# StaticPlatformMain_v1.net
KiCad netlist of a schematic drawn in EAGLE
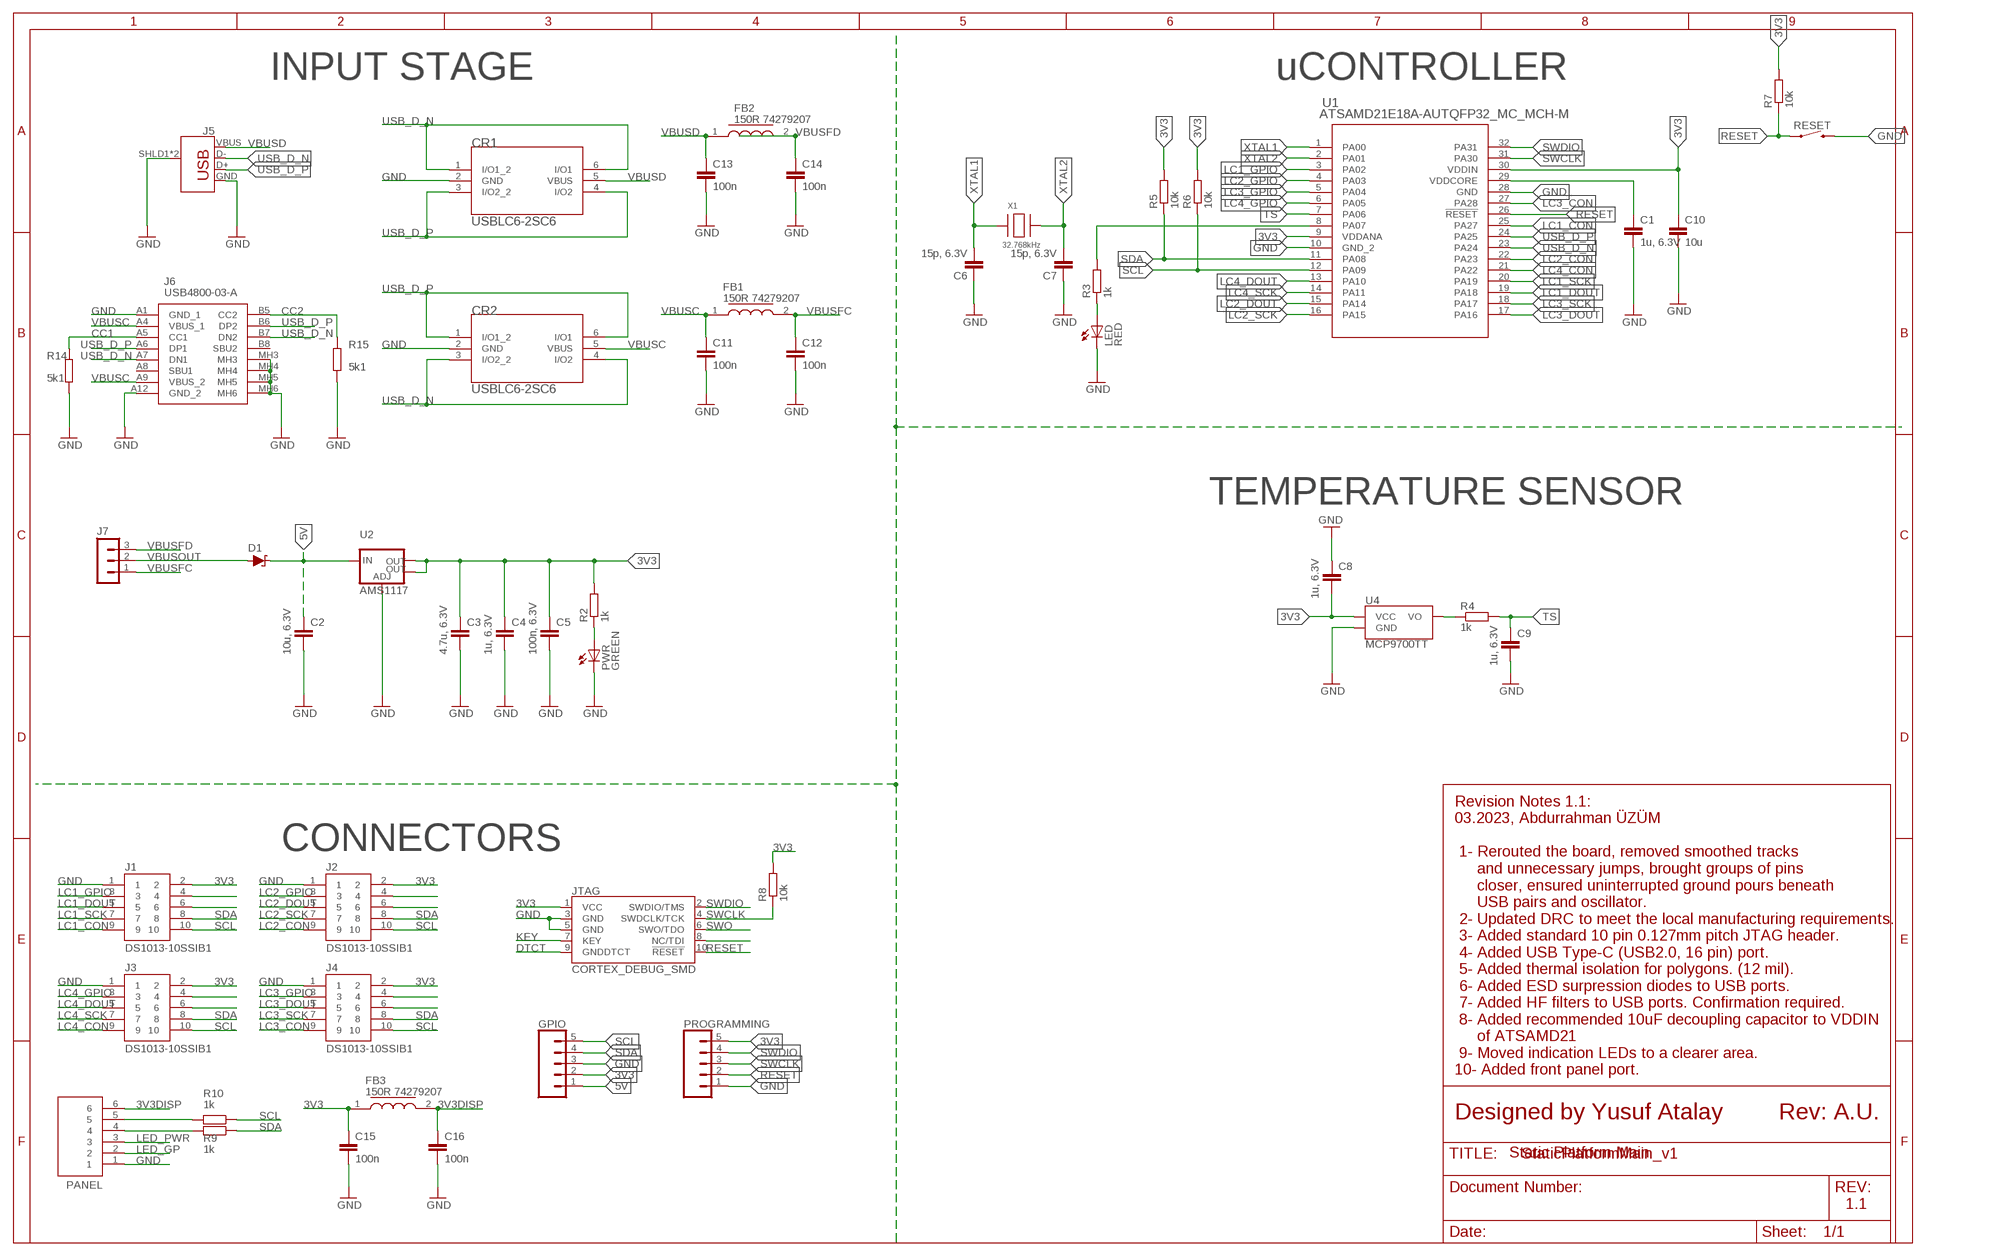
[diagram p0: schematic, sheet 1]

(export (version "E")
  (design (tool "Eeschema 10.0.6"))
  (components
    (comp (ref "C1")
      (value "1u, 6.3V")
      (footprint "eagle-import:C0805")
      (libsource (lib "eagle-import") (part "C-EUC0805"))
    )
    (comp (ref "C2")
      (value "10u, 6.3V")
      (footprint "eagle-import:C0805")
      (libsource (lib "eagle-import") (part "C-EUC0805"))
    )
    (comp (ref "C3")
      (value "4.7u, 6.3V")
      (footprint "eagle-import:C0805")
      (libsource (lib "eagle-import") (part "C-EUC0805"))
    )
    (comp (ref "C4")
      (value "1u, 6.3V")
      (footprint "eagle-import:C0805")
      (libsource (lib "eagle-import") (part "C-EUC0805"))
    )
    (comp (ref "C5")
      (value "100n, 6.3V")
      (footprint "eagle-import:C0805")
      (libsource (lib "eagle-import") (part "C-EUC0805"))
    )
    (comp (ref "C6")
      (value "15p, 6.3V")
      (footprint "eagle-import:C0805")
      (libsource (lib "eagle-import") (part "C-EUC0805"))
    )
    (comp (ref "C7")
      (value "15p, 6.3V")
      (footprint "eagle-import:C0805")
      (libsource (lib "eagle-import") (part "C-EUC0805"))
    )
    (comp (ref "C8")
      (value "1u, 6.3V")
      (footprint "eagle-import:C0805")
      (libsource (lib "eagle-import") (part "C-EUC0805"))
    )
    (comp (ref "C9")
      (value "1u, 6.3V")
      (footprint "eagle-import:C0805")
      (libsource (lib "eagle-import") (part "C-EUC0805"))
    )
    (comp (ref "C10")
      (value "10u")
      (footprint "eagle-import:C0805")
      (libsource (lib "eagle-import") (part "C-EUC0805"))
    )
    (comp (ref "C11")
      (value "100n")
      (footprint "eagle-import:C0805")
      (libsource (lib "eagle-import") (part "C-EUC0805"))
    )
    (comp (ref "C12")
      (value "100n")
      (footprint "eagle-import:C0805")
      (libsource (lib "eagle-import") (part "C-EUC0805"))
    )
    (comp (ref "C13")
      (value "100n")
      (footprint "eagle-import:C0805")
      (libsource (lib "eagle-import") (part "C-EUC0805"))
    )
    (comp (ref "C14")
      (value "100n")
      (footprint "eagle-import:C0805")
      (libsource (lib "eagle-import") (part "C-EUC0805"))
    )
    (comp (ref "C15")
      (value "100n")
      (footprint "eagle-import:C0805")
      (libsource (lib "eagle-import") (part "C-EUC0805"))
    )
    (comp (ref "C16")
      (value "100n")
      (footprint "eagle-import:C0805")
      (libsource (lib "eagle-import") (part "C-EUC0805"))
    )
    (comp (ref "CR1")
      (value "USBLC6-2SC6")
      (footprint "eagle-import:SOT23-6L_STM")
      (fields (field (name "COPYRIGHT") "Copyright (C) 2023 Ultra Librarian. All rights reserved."))
      (libsource (lib "eagle-import") (part "USBLC6-2SC6"))
    )
    (comp (ref "CR2")
      (value "USBLC6-2SC6")
      (footprint "eagle-import:SOT23-6L_STM")
      (fields (field (name "COPYRIGHT") "Copyright (C) 2023 Ultra Librarian. All rights reserved."))
      (libsource (lib "eagle-import") (part "USBLC6-2SC6"))
    )
    (comp (ref "D1")
      (value "3A/10V/280mV")
      (footprint "eagle-import:SOD-323")
      (libsource (lib "eagle-import") (part "DIODE-SCHOTTKY-BAT60A"))
    )
    (comp (ref "FB1")
      (value "150R 74279207")
      (footprint "eagle-import:CAPC2012X90N")
      (fields
        (field (name "MANUFACTURER_PART_NUMBER") "74279207")
        (field (name "MOUSER_PART_NUMBER") "710-74279207")
      )
      (libsource (lib "eagle-import") (part "74279207"))
    )
    (comp (ref "FB2")
      (value "150R 74279207")
      (footprint "eagle-import:CAPC2012X90N")
      (fields
        (field (name "MANUFACTURER_PART_NUMBER") "74279207")
        (field (name "MOUSER_PART_NUMBER") "710-74279207")
      )
      (libsource (lib "eagle-import") (part "74279207"))
    )
    (comp (ref "FB3")
      (value "150R 74279207")
      (footprint "eagle-import:CAPC2012X90N")
      (fields
        (field (name "MANUFACTURER_PART_NUMBER") "74279207")
        (field (name "MOUSER_PART_NUMBER") "710-74279207")
      )
      (libsource (lib "eagle-import") (part "74279207"))
    )
    (comp (ref "GPIO")
      (value "CONN_05NO_SILK")
      (footprint "eagle-import:1X05_NO_SILK")
      (libsource (lib "eagle-import") (part "CONN_05NO_SILK"))
    )
    (comp (ref "J1")
      (value "DS1013-10SSIB1")
      (footprint "eagle-import:CONNFLY_DS1013-10SSIB1")
      (fields (field (name "MF") "Connfly"))
      (libsource (lib "eagle-import") (part "DS1013-10SSIB1"))
    )
    (comp (ref "J2")
      (value "DS1013-10SSIB1")
      (footprint "eagle-import:CONNFLY_DS1013-10SSIB1")
      (fields (field (name "MF") "Connfly"))
      (libsource (lib "eagle-import") (part "DS1013-10SSIB1"))
    )
    (comp (ref "J3")
      (value "DS1013-10SSIB1")
      (footprint "eagle-import:CONNFLY_DS1013-10SSIB1")
      (fields (field (name "MF") "Connfly"))
      (libsource (lib "eagle-import") (part "DS1013-10SSIB1"))
    )
    (comp (ref "J4")
      (value "DS1013-10SSIB1")
      (footprint "eagle-import:CONNFLY_DS1013-10SSIB1")
      (fields (field (name "MF") "Connfly"))
      (libsource (lib "eagle-import") (part "DS1013-10SSIB1"))
    )
    (comp (ref "J5")
      (value "USB_B_PTH")
      (footprint "eagle-import:USB-B-PTH")
      (libsource (lib "eagle-import") (part "USB_B_PTH"))
    )
    (comp (ref "J6")
      (value "USB4800-03-A")
      (footprint "eagle-import:USB480003A")
      (fields (field (name "MOUSER_PART_NUMBER") "640-USB4800-03-A"))
      (libsource (lib "eagle-import") (part "USB4800-03-A"))
    )
    (comp (ref "J7")
      (value "MA03-1")
      (footprint "eagle-import:MA03-1")
      (libsource (lib "eagle-import") (part "MA03-1"))
    )
    (comp (ref "JTAG")
      (value "CORTEX_DEBUG_SMD")
      (footprint "eagle-import:SAMTECH_FTSH-105-01")
      (libsource (lib "eagle-import") (part "CORTEX_DEBUG_SMD"))
    )
    (comp (ref "LED")
      (value "RED")
      (footprint "eagle-import:CHIPLED_0805")
      (libsource (lib "eagle-import") (part "LEDCHIPLED_0805"))
    )
    (comp (ref "PANEL")
      (value "S3B-XH-A(LF)(SN)")
      (footprint "eagle-import:JST_S3B-XH-A(LF)(SN)")
      (fields (field (name "MF") "JST Sales"))
      (libsource (lib "eagle-import") (part "S3B-XH-A(LF)(SN)"))
    )
    (comp (ref "PROGRAMMING")
      (value "CONN_05NO_SILK")
      (footprint "eagle-import:1X05_NO_SILK")
      (libsource (lib "eagle-import") (part "CONN_05NO_SILK"))
    )
    (comp (ref "PWR")
      (value "GREEN")
      (footprint "eagle-import:CHIPLED_0805")
      (libsource (lib "eagle-import") (part "LEDCHIPLED_0805"))
    )
    (comp (ref "R2")
      (value "1k")
      (footprint "eagle-import:R0805")
      (libsource (lib "eagle-import") (part "R-EU_R0805"))
    )
    (comp (ref "R3")
      (value "1k")
      (footprint "eagle-import:R0805")
      (libsource (lib "eagle-import") (part "R-EU_R0805"))
    )
    (comp (ref "R4")
      (value "1k")
      (footprint "eagle-import:R0805")
      (libsource (lib "eagle-import") (part "R-EU_R0805"))
    )
    (comp (ref "R5")
      (value "10k")
      (footprint "eagle-import:R0805")
      (libsource (lib "eagle-import") (part "R-EU_R0805"))
    )
    (comp (ref "R6")
      (value "10k")
      (footprint "eagle-import:R0805")
      (libsource (lib "eagle-import") (part "R-EU_R0805"))
    )
    (comp (ref "R7")
      (value "10k")
      (footprint "eagle-import:R0805")
      (libsource (lib "eagle-import") (part "R-EU_R0805"))
    )
    (comp (ref "R8")
      (value "10k")
      (footprint "eagle-import:R0805")
      (libsource (lib "eagle-import") (part "R-EU_R0805"))
    )
    (comp (ref "R9")
      (value "1k")
      (footprint "eagle-import:R0805")
      (libsource (lib "eagle-import") (part "R-EU_R0805"))
    )
    (comp (ref "R10")
      (value "1k")
      (footprint "eagle-import:R0805")
      (libsource (lib "eagle-import") (part "R-EU_R0805"))
    )
    (comp (ref "R14")
      (value "5k1")
      (footprint "eagle-import:R0805")
      (libsource (lib "eagle-import") (part "R-EU_R0805"))
    )
    (comp (ref "R15")
      (value "5k1")
      (footprint "eagle-import:R0805")
      (libsource (lib "eagle-import") (part "R-EU_R0805"))
    )
    (comp (ref "RESET")
      (value "MOMENTARY-SWITCH-SPST-SMD-6.0X3.5MM")
      (footprint "eagle-import:TACTILE_SWITCH_SMD_6.0X3.5MM")
      (libsource (lib "eagle-import") (part "MOMENTARY-SWITCH-SPST-SMD-6.0X3.5MM"))
    )
    (comp (ref "U1")
      (value "ATSAMD21E18A-AUTQFP32_MC_MCH-M")
      (footprint "eagle-import:TQFP32_MC_MCH-M")
      (fields
        (field (name "MANUFACTURER_PART_NUMBER") "ATSAMD21E18A-AU")
        (field (name "COPYRIGHT") "Copyright (C) 2022 Ultra Librarian. All rights reserved.")
      )
      (libsource (lib "eagle-import") (part "ATSAMD21E18A-AUTQFP32_MC_MCH-M"))
    )
    (comp (ref "U2")
      (value "AMS1117")
      (footprint "eagle-import:SOT223")
      (libsource (lib "eagle-import") (part "V_REG_LM1117SOT223"))
    )
    (comp (ref "U4")
      (value "MCP9700TT")
      (footprint "eagle-import:SOT23-3")
      (libsource (lib "eagle-import") (part "MCP9700TT"))
    )
    (comp (ref "X1")
      (value "32.768kHz")
      (footprint "eagle-import:XTAL3215")
      (libsource (lib "eagle-import") (part "XTAL-3.2X1.5"))
    )
  )
  (nets
    (net (code "1") (name "/3V3DISP") (class "Default")
      (node (ref "C16") (pin "1") (pinfunction "1_1") (pintype "passive"))
      (node (ref "FB3") (pin "2") (pinfunction "2_2") (pintype "bidirectional"))
      (node (ref "PANEL") (pin "6") (pinfunction "6_6") (pintype "passive"))
    )
    (net (code "2") (name "/CC1") (class "Default")
      (node (ref "J6") (pin "A5") (pinfunction "CC1_A5") (pintype "bidirectional"))
      (node (ref "R14") (pin "2") (pinfunction "2_2") (pintype "passive"))
    )
    (net (code "3") (name "/CC2") (class "Default")
      (node (ref "J6") (pin "B5") (pinfunction "CC2_B5") (pintype "bidirectional"))
      (node (ref "R15") (pin "2") (pinfunction "2_2") (pintype "passive"))
    )
    (net (code "4") (name "/DTCT") (class "Default")
      (node (ref "JTAG") (pin "9") (pinfunction "GNDDTCT_9") (pintype "bidirectional"))
    )
    (net (code "5") (name "/KEY") (class "Default")
      (node (ref "JTAG") (pin "7") (pinfunction "KEY_7") (pintype "bidirectional"))
    )
    (net (code "6") (name "/LED_GP") (class "Default")
      (node (ref "LED") (pin "A") (pinfunction "A_A") (pintype "passive"))
      (node (ref "PANEL") (pin "2") (pinfunction "2_2") (pintype "passive"))
      (node (ref "R3") (pin "1") (pinfunction "1_1") (pintype "passive"))
    )
    (net (code "7") (name "/LED_PWR") (class "Default")
      (node (ref "PANEL") (pin "3") (pinfunction "3_3") (pintype "passive"))
      (node (ref "PWR") (pin "A") (pinfunction "A_A") (pintype "passive"))
      (node (ref "R2") (pin "1") (pinfunction "1_1") (pintype "passive"))
    )
    (net (code "8") (name "/SWO") (class "Default")
      (node (ref "JTAG") (pin "6") (pinfunction "SWO/TDO_6") (pintype "bidirectional"))
    )
    (net (code "9") (name "/VBUSC") (class "Default")
      (node (ref "C11") (pin "1") (pinfunction "1_1") (pintype "passive"))
      (node (ref "CR2") (pin "5") (pinfunction "VBUS_5") (pintype "power_in"))
      (node (ref "FB1") (pin "1") (pinfunction "1_1") (pintype "bidirectional"))
      (node (ref "J6") (pin "A4") (pinfunction "VBUS_1_A4") (pintype "bidirectional"))
      (node (ref "J6") (pin "A9") (pinfunction "VBUS_2_A9") (pintype "bidirectional"))
    )
    (net (code "10") (name "/VBUSD") (class "Default")
      (node (ref "C13") (pin "1") (pinfunction "1_1") (pintype "passive"))
      (node (ref "CR1") (pin "5") (pinfunction "VBUS_5") (pintype "power_in"))
      (node (ref "FB2") (pin "1") (pinfunction "1_1") (pintype "bidirectional"))
      (node (ref "J5") (pin "VBUS") (pinfunction "VBUS_VBUS") (pintype "power_in"))
    )
    (net (code "11") (name "/VBUSFC") (class "Default")
      (node (ref "C12") (pin "1") (pinfunction "1_1") (pintype "passive"))
      (node (ref "FB1") (pin "2") (pinfunction "2_2") (pintype "bidirectional"))
      (node (ref "J7") (pin "1") (pinfunction "1_1") (pintype "passive"))
    )
    (net (code "12") (name "/VBUSFD") (class "Default")
      (node (ref "C14") (pin "1") (pinfunction "1_1") (pintype "passive"))
      (node (ref "FB2") (pin "2") (pinfunction "2_2") (pintype "bidirectional"))
      (node (ref "J7") (pin "3") (pinfunction "3_3") (pintype "passive"))
    )
    (net (code "13") (name "/VBUSOUT") (class "Default")
      (node (ref "D1") (pin "A") (pinfunction "A_A") (pintype "passive"))
      (node (ref "J7") (pin "2") (pinfunction "2_2") (pintype "passive"))
    )
    (net (code "14") (name "3V3") (class "Default")
      (node (ref "C10") (pin "1") (pinfunction "1_1") (pintype "passive"))
      (node (ref "C15") (pin "1") (pinfunction "1_1") (pintype "passive"))
      (node (ref "C3") (pin "1") (pinfunction "1_1") (pintype "passive"))
      (node (ref "C4") (pin "1") (pinfunction "1_1") (pintype "passive"))
      (node (ref "C5") (pin "1") (pinfunction "1_1") (pintype "passive"))
      (node (ref "C8") (pin "2") (pinfunction "2_2") (pintype "passive"))
      (node (ref "FB3") (pin "1") (pinfunction "1_1") (pintype "bidirectional"))
      (node (ref "GPIO") (pin "2") (pinfunction "2_2") (pintype "passive"))
      (node (ref "J1") (pin "2") (pinfunction "2_2") (pintype "passive"))
      (node (ref "J2") (pin "2") (pinfunction "2_2") (pintype "passive"))
      (node (ref "J3") (pin "2") (pinfunction "2_2") (pintype "passive"))
      (node (ref "J4") (pin "2") (pinfunction "2_2") (pintype "passive"))
      (node (ref "JTAG") (pin "1") (pinfunction "VCC_1") (pintype "bidirectional"))
      (node (ref "PROGRAMMING") (pin "5") (pinfunction "5_5") (pintype "passive"))
      (node (ref "R2") (pin "2") (pinfunction "2_2") (pintype "passive"))
      (node (ref "R5") (pin "2") (pinfunction "2_2") (pintype "passive"))
      (node (ref "R6") (pin "2") (pinfunction "2_2") (pintype "passive"))
      (node (ref "R7") (pin "2") (pinfunction "2_2") (pintype "passive"))
      (node (ref "R8") (pin "2") (pinfunction "2_2") (pintype "passive"))
      (node (ref "U1") (pin "30") (pinfunction "VDDIN_30") (pintype "power_in"))
      (node (ref "U1") (pin "9") (pinfunction "VDDANA_9") (pintype "power_in"))
      (node (ref "U2") (pin "2") (pinfunction "OUT_2") (pintype "output"))
      (node (ref "U2") (pin "4") (pinfunction "OUT_4") (pintype "output"))
      (node (ref "U4") (pin "1") (pinfunction "VCC_1") (pintype "bidirectional"))
    )
    (net (code "15") (name "5V") (class "Default")
      (node (ref "C2") (pin "1") (pinfunction "1_1") (pintype "passive"))
      (node (ref "D1") (pin "C") (pinfunction "C_C") (pintype "passive"))
      (node (ref "GPIO") (pin "1") (pinfunction "1_1") (pintype "passive"))
      (node (ref "U2") (pin "3") (pinfunction "IN_3") (pintype "input"))
    )
    (net (code "16") (name "GND") (class "Default")
      (node (ref "C1") (pin "2") (pinfunction "2_2") (pintype "passive"))
      (node (ref "C10") (pin "2") (pinfunction "2_2") (pintype "passive"))
      (node (ref "C11") (pin "2") (pinfunction "2_2") (pintype "passive"))
      (node (ref "C12") (pin "2") (pinfunction "2_2") (pintype "passive"))
      (node (ref "C13") (pin "2") (pinfunction "2_2") (pintype "passive"))
      (node (ref "C14") (pin "2") (pinfunction "2_2") (pintype "passive"))
      (node (ref "C15") (pin "2") (pinfunction "2_2") (pintype "passive"))
      (node (ref "C16") (pin "2") (pinfunction "2_2") (pintype "passive"))
      (node (ref "C2") (pin "2") (pinfunction "2_2") (pintype "passive"))
      (node (ref "C3") (pin "2") (pinfunction "2_2") (pintype "passive"))
      (node (ref "C4") (pin "2") (pinfunction "2_2") (pintype "passive"))
      (node (ref "C5") (pin "2") (pinfunction "2_2") (pintype "passive"))
      (node (ref "C6") (pin "1") (pinfunction "1_1") (pintype "passive"))
      (node (ref "C7") (pin "1") (pinfunction "1_1") (pintype "passive"))
      (node (ref "C8") (pin "1") (pinfunction "1_1") (pintype "passive"))
      (node (ref "C9") (pin "2") (pinfunction "2_2") (pintype "passive"))
      (node (ref "CR1") (pin "2") (pinfunction "GND_2") (pintype "power_in"))
      (node (ref "CR2") (pin "2") (pinfunction "GND_2") (pintype "power_in"))
      (node (ref "GPIO") (pin "3") (pinfunction "3_3") (pintype "passive"))
      (node (ref "J1") (pin "1") (pinfunction "1_1") (pintype "passive"))
      (node (ref "J2") (pin "1") (pinfunction "1_1") (pintype "passive"))
      (node (ref "J3") (pin "1") (pinfunction "1_1") (pintype "passive"))
      (node (ref "J4") (pin "1") (pinfunction "1_1") (pintype "passive"))
      (node (ref "J5") (pin "GND") (pinfunction "GND_GND") (pintype "power_in"))
      (node (ref "J5") (pin "SHLD1") (pinfunction "SHIELD_SHLD1") (pintype "bidirectional"))
      (node (ref "J5") (pin "SHLD2") (pinfunction "SHIELD_SHLD2") (pintype "bidirectional"))
      (node (ref "J6") (pin "A1") (pinfunction "GND_1_A1") (pintype "bidirectional"))
      (node (ref "J6") (pin "A12") (pinfunction "GND_2_A12") (pintype "bidirectional"))
      (node (ref "J6") (pin "MH3") (pinfunction "MH3_MH3") (pintype "bidirectional"))
      (node (ref "J6") (pin "MH4") (pinfunction "MH4_MH4") (pintype "bidirectional"))
      (node (ref "J6") (pin "MH5") (pinfunction "MH5_MH5") (pintype "bidirectional"))
      (node (ref "J6") (pin "MH6") (pinfunction "MH6_MH6") (pintype "bidirectional"))
      (node (ref "JTAG") (pin "3") (pinfunction "GND_3") (pintype "bidirectional"))
      (node (ref "JTAG") (pin "5") (pinfunction "GND_5") (pintype "bidirectional"))
      (node (ref "LED") (pin "C") (pinfunction "C_C") (pintype "passive"))
      (node (ref "PANEL") (pin "1") (pinfunction "1_1") (pintype "passive"))
      (node (ref "PROGRAMMING") (pin "1") (pinfunction "1_1") (pintype "passive"))
      (node (ref "PWR") (pin "C") (pinfunction "C_C") (pintype "passive"))
      (node (ref "R14") (pin "1") (pinfunction "1_1") (pintype "passive"))
      (node (ref "R15") (pin "1") (pinfunction "1_1") (pintype "passive"))
      (node (ref "RESET") (pin "2") (pinfunction "2_2") (pintype "passive"))
      (node (ref "U1") (pin "10") (pinfunction "GND_2_10") (pintype "passive"))
      (node (ref "U1") (pin "28") (pinfunction "GND_28") (pintype "passive"))
      (node (ref "U2") (pin "1") (pinfunction "ADJ_1") (pintype "input"))
      (node (ref "U4") (pin "3") (pinfunction "GND_3") (pintype "bidirectional"))
    )
    (net (code "17") (name "LC1_CON") (class "Default")
      (node (ref "J1") (pin "9") (pinfunction "9_9") (pintype "passive"))
      (node (ref "U1") (pin "25") (pinfunction "PA27_25") (pintype "bidirectional"))
    )
    (net (code "18") (name "LC1_DOUT") (class "Default")
      (node (ref "J1") (pin "5") (pinfunction "5_5") (pintype "passive"))
      (node (ref "U1") (pin "19") (pinfunction "PA18_19") (pintype "bidirectional"))
    )
    (net (code "19") (name "LC1_GPIO") (class "Default")
      (node (ref "J1") (pin "3") (pinfunction "3_3") (pintype "passive"))
      (node (ref "U1") (pin "3") (pinfunction "PA02_3") (pintype "bidirectional"))
    )
    (net (code "20") (name "LC1_SCK") (class "Default")
      (node (ref "J1") (pin "7") (pinfunction "7_7") (pintype "passive"))
      (node (ref "U1") (pin "20") (pinfunction "PA19_20") (pintype "bidirectional"))
    )
    (net (code "21") (name "LC2_CON") (class "Default")
      (node (ref "J2") (pin "9") (pinfunction "9_9") (pintype "passive"))
      (node (ref "U1") (pin "22") (pinfunction "PA23_22") (pintype "bidirectional"))
    )
    (net (code "22") (name "LC2_DOUT") (class "Default")
      (node (ref "J2") (pin "5") (pinfunction "5_5") (pintype "passive"))
      (node (ref "U1") (pin "15") (pinfunction "PA14_15") (pintype "bidirectional"))
    )
    (net (code "23") (name "LC2_GPIO") (class "Default")
      (node (ref "J2") (pin "3") (pinfunction "3_3") (pintype "passive"))
      (node (ref "U1") (pin "4") (pinfunction "PA03_4") (pintype "bidirectional"))
    )
    (net (code "24") (name "LC2_SCK") (class "Default")
      (node (ref "J2") (pin "7") (pinfunction "7_7") (pintype "passive"))
      (node (ref "U1") (pin "16") (pinfunction "PA15_16") (pintype "bidirectional"))
    )
    (net (code "25") (name "LC3_CON") (class "Default")
      (node (ref "J4") (pin "9") (pinfunction "9_9") (pintype "passive"))
      (node (ref "U1") (pin "27") (pinfunction "PA28_27") (pintype "bidirectional"))
    )
    (net (code "26") (name "LC3_DOUT") (class "Default")
      (node (ref "J4") (pin "5") (pinfunction "5_5") (pintype "passive"))
      (node (ref "U1") (pin "17") (pinfunction "PA16_17") (pintype "bidirectional"))
    )
    (net (code "27") (name "LC3_GPIO") (class "Default")
      (node (ref "J4") (pin "3") (pinfunction "3_3") (pintype "passive"))
      (node (ref "U1") (pin "5") (pinfunction "PA04_5") (pintype "bidirectional"))
    )
    (net (code "28") (name "LC3_SCK") (class "Default")
      (node (ref "J4") (pin "7") (pinfunction "7_7") (pintype "passive"))
      (node (ref "U1") (pin "18") (pinfunction "PA17_18") (pintype "bidirectional"))
    )
    (net (code "29") (name "LC4_CON") (class "Default")
      (node (ref "J3") (pin "9") (pinfunction "9_9") (pintype "passive"))
      (node (ref "U1") (pin "21") (pinfunction "PA22_21") (pintype "bidirectional"))
    )
    (net (code "30") (name "LC4_DOUT") (class "Default")
      (node (ref "J3") (pin "5") (pinfunction "5_5") (pintype "passive"))
      (node (ref "U1") (pin "13") (pinfunction "PA10_13") (pintype "bidirectional"))
    )
    (net (code "31") (name "LC4_GPIO") (class "Default")
      (node (ref "J3") (pin "3") (pinfunction "3_3") (pintype "passive"))
      (node (ref "U1") (pin "6") (pinfunction "PA05_6") (pintype "bidirectional"))
    )
    (net (code "32") (name "LC4_SCK") (class "Default")
      (node (ref "J3") (pin "7") (pinfunction "7_7") (pintype "passive"))
      (node (ref "U1") (pin "14") (pinfunction "PA11_14") (pintype "bidirectional"))
    )
    (net (code "33") (name "Net-(PANEL-Pad4)") (class "Default")
      (node (ref "PANEL") (pin "4") (pinfunction "4_4") (pintype "passive"))
      (node (ref "R9") (pin "2") (pinfunction "2_2") (pintype "passive"))
    )
    (net (code "34") (name "Net-(PANEL-Pad5)") (class "Default")
      (node (ref "PANEL") (pin "5") (pinfunction "5_5") (pintype "passive"))
      (node (ref "R10") (pin "2") (pinfunction "2_2") (pintype "passive"))
    )
    (net (code "35") (name "Net-(U1-PA07)") (class "Default")
      (node (ref "R3") (pin "2") (pinfunction "2_2") (pintype "passive"))
      (node (ref "U1") (pin "8") (pinfunction "PA07_8") (pintype "bidirectional"))
    )
    (net (code "36") (name "Net-(U1-VDDCORE)") (class "Default")
      (node (ref "C1") (pin "1") (pinfunction "1_1") (pintype "passive"))
      (node (ref "U1") (pin "29") (pinfunction "VDDCORE_29") (pintype "power_in"))
    )
    (net (code "37") (name "Net-(U4-VO)") (class "Default")
      (node (ref "R4") (pin "1") (pinfunction "1_1") (pintype "passive"))
      (node (ref "U4") (pin "2") (pinfunction "VO_2") (pintype "bidirectional"))
    )
    (net (code "38") (name "RESET") (class "Default")
      (node (ref "JTAG") (pin "10") (pinfunction "~{RESET}_10") (pintype "bidirectional"))
      (node (ref "PROGRAMMING") (pin "2") (pinfunction "2_2") (pintype "passive"))
      (node (ref "R7") (pin "1") (pinfunction "1_1") (pintype "passive"))
      (node (ref "RESET") (pin "1") (pinfunction "1_1") (pintype "passive"))
      (node (ref "U1") (pin "26") (pinfunction "~{RESET}_26") (pintype "passive"))
    )
    (net (code "39") (name "SCL") (class "Default")
      (node (ref "GPIO") (pin "5") (pinfunction "5_5") (pintype "passive"))
      (node (ref "J1") (pin "10") (pinfunction "10_10") (pintype "passive"))
      (node (ref "J2") (pin "10") (pinfunction "10_10") (pintype "passive"))
      (node (ref "J3") (pin "10") (pinfunction "10_10") (pintype "passive"))
      (node (ref "J4") (pin "10") (pinfunction "10_10") (pintype "passive"))
      (node (ref "R10") (pin "1") (pinfunction "1_1") (pintype "passive"))
      (node (ref "R6") (pin "1") (pinfunction "1_1") (pintype "passive"))
      (node (ref "U1") (pin "12") (pinfunction "PA09_12") (pintype "bidirectional"))
    )
    (net (code "40") (name "SDA") (class "Default")
      (node (ref "GPIO") (pin "4") (pinfunction "4_4") (pintype "passive"))
      (node (ref "J1") (pin "8") (pinfunction "8_8") (pintype "passive"))
      (node (ref "J2") (pin "8") (pinfunction "8_8") (pintype "passive"))
      (node (ref "J3") (pin "8") (pinfunction "8_8") (pintype "passive"))
      (node (ref "J4") (pin "8") (pinfunction "8_8") (pintype "passive"))
      (node (ref "R5") (pin "1") (pinfunction "1_1") (pintype "passive"))
      (node (ref "R9") (pin "1") (pinfunction "1_1") (pintype "passive"))
      (node (ref "U1") (pin "11") (pinfunction "PA08_11") (pintype "bidirectional"))
    )
    (net (code "41") (name "SWCLK") (class "Default")
      (node (ref "JTAG") (pin "4") (pinfunction "SWDCLK/TCK_4") (pintype "bidirectional"))
      (node (ref "PROGRAMMING") (pin "3") (pinfunction "3_3") (pintype "passive"))
      (node (ref "R8") (pin "1") (pinfunction "1_1") (pintype "passive"))
      (node (ref "U1") (pin "31") (pinfunction "PA30_31") (pintype "bidirectional"))
    )
    (net (code "42") (name "SWDIO") (class "Default")
      (node (ref "JTAG") (pin "2") (pinfunction "SWDIO/TMS_2") (pintype "bidirectional"))
      (node (ref "PROGRAMMING") (pin "4") (pinfunction "4_4") (pintype "passive"))
      (node (ref "U1") (pin "32") (pinfunction "PA31_32") (pintype "bidirectional"))
    )
    (net (code "43") (name "TS") (class "Default")
      (node (ref "C9") (pin "1") (pinfunction "1_1") (pintype "passive"))
      (node (ref "R4") (pin "2") (pinfunction "2_2") (pintype "passive"))
      (node (ref "U1") (pin "7") (pinfunction "PA06_7") (pintype "bidirectional"))
    )
    (net (code "44") (name "USB_D_N") (class "Default")
      (node (ref "CR1") (pin "1") (pinfunction "I/O1_2_1") (pintype "bidirectional"))
      (node (ref "CR1") (pin "6") (pinfunction "I/O1_6") (pintype "bidirectional"))
      (node (ref "CR2") (pin "3") (pinfunction "I/O2_2_3") (pintype "bidirectional"))
      (node (ref "CR2") (pin "4") (pinfunction "I/O2_4") (pintype "bidirectional"))
      (node (ref "J5") (pin "D-") (pinfunction "D-_D-") (pintype "bidirectional"))
      (node (ref "J6") (pin "A7") (pinfunction "DN1_A7") (pintype "bidirectional"))
      (node (ref "J6") (pin "B7") (pinfunction "DN2_B7") (pintype "bidirectional"))
      (node (ref "U1") (pin "23") (pinfunction "PA24_23") (pintype "bidirectional"))
    )
    (net (code "45") (name "USB_D_P") (class "Default")
      (node (ref "CR1") (pin "3") (pinfunction "I/O2_2_3") (pintype "bidirectional"))
      (node (ref "CR1") (pin "4") (pinfunction "I/O2_4") (pintype "bidirectional"))
      (node (ref "CR2") (pin "1") (pinfunction "I/O1_2_1") (pintype "bidirectional"))
      (node (ref "CR2") (pin "6") (pinfunction "I/O1_6") (pintype "bidirectional"))
      (node (ref "J5") (pin "D+") (pinfunction "D+_D+") (pintype "bidirectional"))
      (node (ref "J6") (pin "A6") (pinfunction "DP1_A6") (pintype "bidirectional"))
      (node (ref "J6") (pin "B6") (pinfunction "DP2_B6") (pintype "bidirectional"))
      (node (ref "U1") (pin "24") (pinfunction "PA25_24") (pintype "bidirectional"))
    )
    (net (code "46") (name "XTAL1") (class "Default")
      (node (ref "C6") (pin "2") (pinfunction "2_2") (pintype "passive"))
      (node (ref "U1") (pin "1") (pinfunction "PA00_1") (pintype "bidirectional"))
      (node (ref "X1") (pin "P$1") (pinfunction "P$1_P$1") (pintype "bidirectional"))
    )
    (net (code "47") (name "XTAL2") (class "Default")
      (node (ref "C7") (pin "2") (pinfunction "2_2") (pintype "passive"))
      (node (ref "U1") (pin "2") (pinfunction "PA01_2") (pintype "bidirectional"))
      (node (ref "X1") (pin "P$2") (pinfunction "P$2_P$2") (pintype "bidirectional"))
    )
    (net (code "48") (name "unconnected-(J1-Pad4)") (class "Default")
      (node (ref "J1") (pin "4") (pinfunction "4_4") (pintype "passive"))
    )
    (net (code "49") (name "unconnected-(J1-Pad6)") (class "Default")
      (node (ref "J1") (pin "6") (pinfunction "6_6") (pintype "passive"))
    )
    (net (code "50") (name "unconnected-(J2-Pad4)") (class "Default")
      (node (ref "J2") (pin "4") (pinfunction "4_4") (pintype "passive"))
    )
    (net (code "51") (name "unconnected-(J2-Pad6)") (class "Default")
      (node (ref "J2") (pin "6") (pinfunction "6_6") (pintype "passive"))
    )
    (net (code "52") (name "unconnected-(J3-Pad4)") (class "Default")
      (node (ref "J3") (pin "4") (pinfunction "4_4") (pintype "passive"))
    )
    (net (code "53") (name "unconnected-(J3-Pad6)") (class "Default")
      (node (ref "J3") (pin "6") (pinfunction "6_6") (pintype "passive"))
    )
    (net (code "54") (name "unconnected-(J4-Pad4)") (class "Default")
      (node (ref "J4") (pin "4") (pinfunction "4_4") (pintype "passive"))
    )
    (net (code "55") (name "unconnected-(J4-Pad6)") (class "Default")
      (node (ref "J4") (pin "6") (pinfunction "6_6") (pintype "passive"))
    )
    (net (code "56") (name "unconnected-(J6-SBU1-PadA8)") (class "Default")
      (node (ref "J6") (pin "A8") (pinfunction "SBU1_A8") (pintype "bidirectional"))
    )
    (net (code "57") (name "unconnected-(J6-SBU2-PadB8)") (class "Default")
      (node (ref "J6") (pin "B8") (pinfunction "SBU2_B8") (pintype "bidirectional"))
    )
    (net (code "58") (name "unconnected-(JTAG-NC{slash}TDI-Pad8)") (class "Default")
      (node (ref "JTAG") (pin "8") (pinfunction "NC/TDI_8") (pintype "bidirectional"))
    )
  )
)
